# NAVC_Connectors.net
KiCad netlist of a schematic drawn in Altium Designer
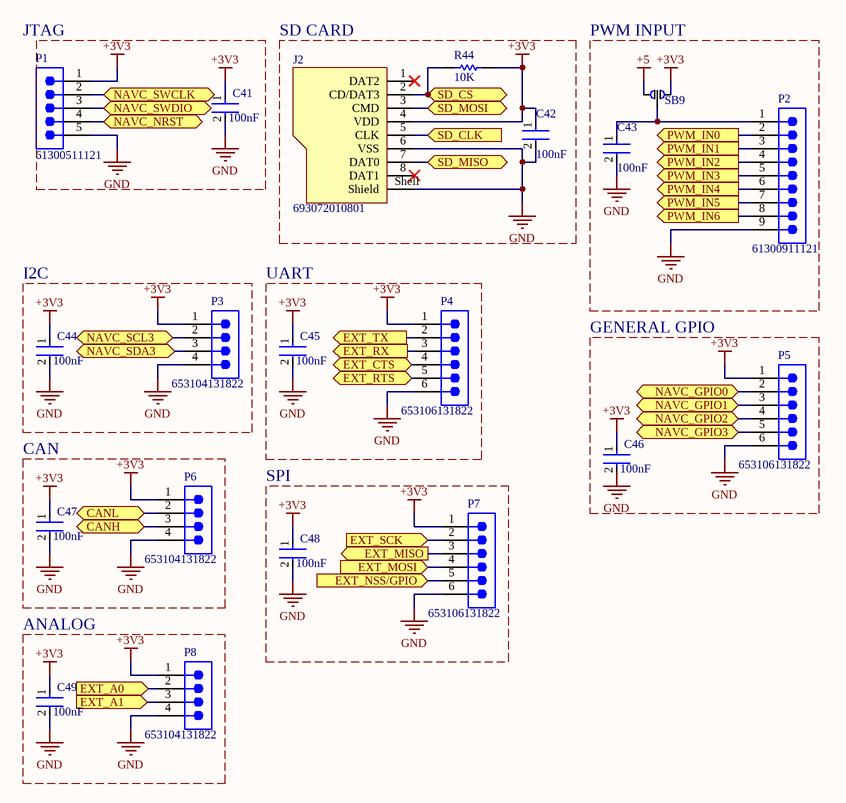
[diagram p0: NAVC_Connectors.SchDoc]

(export (version "E")
  (design (tool "Eeschema 10.0.6"))
  (components
    (comp (ref "C41")
      (value "100nF")
      (footprint "FP-CGA3E-0_3-0_1-IPC_A")
      (description "Cap Ceramic 100nF 50V X7R 10% Pad SMD 0603 +125°C Automotive T/R")
      (fields (field (name "TOLERANCE") "10%") (field (name "VOLTAGE") "50V"))
      (libsource (lib "Altium Content Vault") (part "b4654b650e69147ec39a6b967a45e02"))
    )
    (comp (ref "C42")
      (value "100nF")
      (footprint "FP-CGA3E-0_3-0_1-IPC_A")
      (description "Cap Ceramic 100nF 50V X7R 10% Pad SMD 0603 +125°C Automotive T/R")
      (fields (field (name "TOLERANCE") "10%") (field (name "VOLTAGE") "50V"))
      (libsource (lib "Altium Content Vault") (part "b4654b650e69147ec39a6b967a45e02"))
    )
    (comp (ref "C43")
      (value "100nF")
      (footprint "FP-CGA3E-0_3-0_1-IPC_A")
      (description "Cap Ceramic 100nF 50V X7R 10% Pad SMD 0603 +125°C Automotive T/R")
      (fields (field (name "TOLERANCE") "10%") (field (name "VOLTAGE") "50V"))
      (libsource (lib "Altium Content Vault") (part "b4654b650e69147ec39a6b967a45e02"))
    )
    (comp (ref "C44")
      (value "100nF")
      (footprint "FP-CGA3E-0_3-0_1-IPC_A")
      (description "Cap Ceramic 100nF 50V X7R 10% Pad SMD 0603 +125°C Automotive T/R")
      (fields (field (name "TOLERANCE") "10%") (field (name "VOLTAGE") "50V"))
      (libsource (lib "Altium Content Vault") (part "b4654b650e69147ec39a6b967a45e02"))
    )
    (comp (ref "C45")
      (value "100nF")
      (footprint "FP-CGA3E-0_3-0_1-IPC_A")
      (description "Cap Ceramic 100nF 50V X7R 10% Pad SMD 0603 +125°C Automotive T/R")
      (fields (field (name "TOLERANCE") "10%") (field (name "VOLTAGE") "50V"))
      (libsource (lib "Altium Content Vault") (part "b4654b650e69147ec39a6b967a45e02"))
    )
    (comp (ref "C46")
      (value "100nF")
      (footprint "FP-CGA3E-0_3-0_1-IPC_A")
      (description "Cap Ceramic 100nF 50V X7R 10% Pad SMD 0603 +125°C Automotive T/R")
      (fields (field (name "TOLERANCE") "10%") (field (name "VOLTAGE") "50V"))
      (libsource (lib "Altium Content Vault") (part "b4654b650e69147ec39a6b967a45e02"))
    )
    (comp (ref "C47")
      (value "100nF")
      (footprint "FP-CGA3E-0_3-0_1-IPC_A")
      (description "Cap Ceramic 100nF 50V X7R 10% Pad SMD 0603 +125°C Automotive T/R")
      (fields (field (name "TOLERANCE") "10%") (field (name "VOLTAGE") "50V"))
      (libsource (lib "Altium Content Vault") (part "b4654b650e69147ec39a6b967a45e02"))
    )
    (comp (ref "C48")
      (value "100nF")
      (footprint "FP-CGA3E-0_3-0_1-IPC_A")
      (description "Cap Ceramic 100nF 50V X7R 10% Pad SMD 0603 +125°C Automotive T/R")
      (fields (field (name "TOLERANCE") "10%") (field (name "VOLTAGE") "50V"))
      (libsource (lib "Altium Content Vault") (part "b4654b650e69147ec39a6b967a45e02"))
    )
    (comp (ref "C49")
      (value "100nF")
      (footprint "FP-CGA3E-0_3-0_1-IPC_A")
      (description "Cap Ceramic 100nF 50V X7R 10% Pad SMD 0603 +125°C Automotive T/R")
      (fields (field (name "TOLERANCE") "10%") (field (name "VOLTAGE") "50V"))
      (libsource (lib "Altium Content Vault") (part "b4654b650e69147ec39a6b967a45e02"))
    )
    (comp (ref "J2")
      (value "693072010801")
      (footprint "693072010801")
      (libsource (lib "Altium Content Vault") (part "693072010801"))
    )
    (comp (ref "P1")
      (value "61300511121")
      (footprint "61300511121")
      (libsource (lib "Altium Content Vault") (part "Header_Male_1R_05P"))
    )
    (comp (ref "P2")
      (value "61300911121")
      (footprint "61300911121")
      (libsource (lib "Altium Content Vault") (part "Header_Male_1R_09P"))
    )
    (comp (ref "P3")
      (value "653104131822")
      (footprint "653104131822")
      (libsource (lib "Altium Content Vault") (part "Header_Male_1R_04P"))
    )
    (comp (ref "P4")
      (value "653106131822")
      (footprint "653106131822")
      (libsource (lib "Altium Content Vault") (part "Header_Male_1R_06P"))
    )
    (comp (ref "P5")
      (value "653106131822")
      (footprint "653106131822")
      (libsource (lib "Altium Content Vault") (part "Header_Male_1R_06P"))
    )
    (comp (ref "P6")
      (value "653104131822")
      (footprint "653104131822")
      (libsource (lib "Altium Content Vault") (part "Header_Male_1R_04P"))
    )
    (comp (ref "P7")
      (value "653106131822")
      (footprint "653106131822")
      (libsource (lib "Altium Content Vault") (part "Header_Male_1R_06P"))
    )
    (comp (ref "P8")
      (value "653104131822")
      (footprint "653104131822")
      (libsource (lib "Altium Content Vault") (part "Header_Male_1R_04P"))
    )
    (comp (ref "R44")
      (value "10K")
      (footprint "RESC1608X55X25ML10T15")
      (description "Chip Resistor, 0 Ohm, +/- 5%, 0.1 W, -55 to 155 degC, 0603 (1608 Metric), RoHS, Tape and Reel")
      (fields (field (name "TOLERANCE") "5%") (field (name "MANUFACTURER") "Yageo"))
      (libsource (lib "Altium Content Vault") (part "RES-2"))
    )
    (comp (ref "SB9")
      (value "Solderbridge3P")
      (footprint "SolderBridge3P")
      (libsource (lib "Solder_Bridge") (part "Solderbridge3P"))
    )
  )
  (nets
    (net (code "1") (name "+3V3") (class "Default")
      (node (ref "C41") (pin "1") (pinfunction "1_1") (pintype "passive"))
      (node (ref "C42") (pin "1") (pinfunction "1_1") (pintype "passive"))
      (node (ref "C44") (pin "1") (pinfunction "1_1") (pintype "passive"))
      (node (ref "C45") (pin "1") (pinfunction "1_1") (pintype "passive"))
      (node (ref "C46") (pin "1") (pinfunction "1_1") (pintype "passive"))
      (node (ref "C47") (pin "1") (pinfunction "1_1") (pintype "passive"))
      (node (ref "C48") (pin "1") (pinfunction "1_1") (pintype "passive"))
      (node (ref "C49") (pin "1") (pinfunction "1_1") (pintype "passive"))
      (node (ref "J2") (pin "4") (pinfunction "VDD_4") (pintype "passive"))
      (node (ref "P1") (pin "1") (pinfunction "1_1") (pintype "passive"))
      (node (ref "P3") (pin "1") (pinfunction "1_1") (pintype "passive"))
      (node (ref "P4") (pin "1") (pinfunction "1_1") (pintype "passive"))
      (node (ref "P5") (pin "1") (pinfunction "1_1") (pintype "passive"))
      (node (ref "P6") (pin "1") (pinfunction "1_1") (pintype "passive"))
      (node (ref "P7") (pin "1") (pinfunction "1_1") (pintype "passive"))
      (node (ref "P8") (pin "1") (pinfunction "1_1") (pintype "passive"))
      (node (ref "R44") (pin "2") (pinfunction "2_2") (pintype "passive"))
      (node (ref "SB9") (pin "2") (pinfunction "2_2") (pintype "passive"))
    )
    (net (code "2") (name "+5") (class "Default")
      (node (ref "SB9") (pin "1") (pinfunction "1_1") (pintype "passive"))
    )
    (net (code "3") (name "/CANH") (class "Default")
      (node (ref "P6") (pin "3") (pinfunction "3_3") (pintype "passive"))
    )
    (net (code "4") (name "/CANL") (class "Default")
      (node (ref "P6") (pin "2") (pinfunction "2_2") (pintype "passive"))
    )
    (net (code "5") (name "/EXT_A0") (class "Default")
      (node (ref "P8") (pin "2") (pinfunction "2_2") (pintype "passive"))
    )
    (net (code "6") (name "/EXT_A1") (class "Default")
      (node (ref "P8") (pin "3") (pinfunction "3_3") (pintype "passive"))
    )
    (net (code "7") (name "/EXT_CTS") (class "Default")
      (node (ref "P4") (pin "4") (pinfunction "4_4") (pintype "passive"))
    )
    (net (code "8") (name "/EXT_MISO") (class "Default")
      (node (ref "P7") (pin "3") (pinfunction "3_3") (pintype "passive"))
    )
    (net (code "9") (name "/EXT_MOSI") (class "Default")
      (node (ref "P7") (pin "4") (pinfunction "4_4") (pintype "passive"))
    )
    (net (code "10") (name "/EXT_NSS{slash}GPIO") (class "Default")
      (node (ref "P7") (pin "5") (pinfunction "5_5") (pintype "passive"))
    )
    (net (code "11") (name "/EXT_RTS") (class "Default")
      (node (ref "P4") (pin "5") (pinfunction "5_5") (pintype "passive"))
    )
    (net (code "12") (name "/EXT_RX") (class "Default")
      (node (ref "P4") (pin "3") (pinfunction "3_3") (pintype "passive"))
    )
    (net (code "13") (name "/EXT_SCK") (class "Default")
      (node (ref "P7") (pin "2") (pinfunction "2_2") (pintype "passive"))
    )
    (net (code "14") (name "/EXT_TX") (class "Default")
      (node (ref "P4") (pin "2") (pinfunction "2_2") (pintype "passive"))
    )
    (net (code "15") (name "/NAVC_GPIO0") (class "Default")
      (node (ref "P5") (pin "2") (pinfunction "2_2") (pintype "passive"))
    )
    (net (code "16") (name "/NAVC_GPIO1") (class "Default")
      (node (ref "P5") (pin "3") (pinfunction "3_3") (pintype "passive"))
    )
    (net (code "17") (name "/NAVC_GPIO2") (class "Default")
      (node (ref "P5") (pin "4") (pinfunction "4_4") (pintype "passive"))
    )
    (net (code "18") (name "/NAVC_GPIO3") (class "Default")
      (node (ref "P5") (pin "5") (pinfunction "5_5") (pintype "passive"))
    )
    (net (code "19") (name "/NAVC_NRST") (class "Default")
      (node (ref "P1") (pin "4") (pinfunction "4_4") (pintype "passive"))
    )
    (net (code "20") (name "/NAVC_SCL3") (class "Default")
      (node (ref "P3") (pin "2") (pinfunction "2_2") (pintype "passive"))
    )
    (net (code "21") (name "/NAVC_SDA3") (class "Default")
      (node (ref "P3") (pin "3") (pinfunction "3_3") (pintype "passive"))
    )
    (net (code "22") (name "/NAVC_SWCLK") (class "Default")
      (node (ref "P1") (pin "2") (pinfunction "2_2") (pintype "passive"))
    )
    (net (code "23") (name "/NAVC_SWDIO") (class "Default")
      (node (ref "P1") (pin "3") (pinfunction "3_3") (pintype "passive"))
    )
    (net (code "24") (name "/PWM_IN0") (class "Default")
      (node (ref "P2") (pin "2") (pinfunction "2_2") (pintype "passive"))
    )
    (net (code "25") (name "/PWM_IN1") (class "Default")
      (node (ref "P2") (pin "3") (pinfunction "3_3") (pintype "passive"))
    )
    (net (code "26") (name "/PWM_IN2") (class "Default")
      (node (ref "P2") (pin "4") (pinfunction "4_4") (pintype "passive"))
    )
    (net (code "27") (name "/PWM_IN3") (class "Default")
      (node (ref "P2") (pin "5") (pinfunction "5_5") (pintype "passive"))
    )
    (net (code "28") (name "/PWM_IN4") (class "Default")
      (node (ref "P2") (pin "6") (pinfunction "6_6") (pintype "passive"))
    )
    (net (code "29") (name "/PWM_IN5") (class "Default")
      (node (ref "P2") (pin "7") (pinfunction "7_7") (pintype "passive"))
    )
    (net (code "30") (name "/PWM_IN6") (class "Default")
      (node (ref "P2") (pin "8") (pinfunction "8_8") (pintype "passive"))
    )
    (net (code "31") (name "/SD_CLK") (class "Default")
      (node (ref "J2") (pin "5") (pinfunction "CLK_5") (pintype "passive"))
    )
    (net (code "32") (name "/SD_CS") (class "Default")
      (node (ref "J2") (pin "2") (pinfunction "CD/DAT3_2") (pintype "passive"))
      (node (ref "R44") (pin "1") (pinfunction "1_1") (pintype "passive"))
    )
    (net (code "33") (name "/SD_MISO") (class "Default")
      (node (ref "J2") (pin "7") (pinfunction "DAT0_7") (pintype "passive"))
    )
    (net (code "34") (name "/SD_MOSI") (class "Default")
      (node (ref "J2") (pin "3") (pinfunction "CMD_3") (pintype "passive"))
    )
    (net (code "35") (name "GND") (class "Default")
      (node (ref "C41") (pin "2") (pinfunction "2_2") (pintype "passive"))
      (node (ref "C42") (pin "2") (pinfunction "2_2") (pintype "passive"))
      (node (ref "C43") (pin "2") (pinfunction "2_2") (pintype "passive"))
      (node (ref "C44") (pin "2") (pinfunction "2_2") (pintype "passive"))
      (node (ref "C45") (pin "2") (pinfunction "2_2") (pintype "passive"))
      (node (ref "C46") (pin "2") (pinfunction "2_2") (pintype "passive"))
      (node (ref "C47") (pin "2") (pinfunction "2_2") (pintype "passive"))
      (node (ref "C48") (pin "2") (pinfunction "2_2") (pintype "passive"))
      (node (ref "C49") (pin "2") (pinfunction "2_2") (pintype "passive"))
      (node (ref "J2") (pin "6") (pinfunction "VSS_6") (pintype "passive"))
      (node (ref "J2") (pin "Shell") (pinfunction "Shield_Shell") (pintype "passive"))
      (node (ref "P1") (pin "5") (pinfunction "5_5") (pintype "passive"))
      (node (ref "P2") (pin "9") (pinfunction "9_9") (pintype "passive"))
      (node (ref "P3") (pin "4") (pinfunction "4_4") (pintype "passive"))
      (node (ref "P4") (pin "6") (pinfunction "6_6") (pintype "passive"))
      (node (ref "P5") (pin "6") (pinfunction "6_6") (pintype "passive"))
      (node (ref "P6") (pin "4") (pinfunction "4_4") (pintype "passive"))
      (node (ref "P7") (pin "6") (pinfunction "6_6") (pintype "passive"))
      (node (ref "P8") (pin "4") (pinfunction "4_4") (pintype "passive"))
    )
    (net (code "36") (name "Net-(C43-Pad1)") (class "Default")
      (node (ref "C43") (pin "1") (pinfunction "1_1") (pintype "passive"))
      (node (ref "P2") (pin "1") (pinfunction "1_1") (pintype "passive"))
      (node (ref "SB9") (pin "3") (pinfunction "3_3") (pintype "power_in"))
    )
    (net (code "37") (name "unconnected-(J2-DAT1-Pad8)") (class "Default")
      (node (ref "J2") (pin "8") (pinfunction "DAT1_8") (pintype "passive+no_connect"))
    )
    (net (code "38") (name "unconnected-(J2-DAT2-Pad1)") (class "Default")
      (node (ref "J2") (pin "1") (pinfunction "DAT2_1") (pintype "passive+no_connect"))
    )
  )
)
